# CharlieplexNameTag.net
KiCad netlist of a schematic drawn in EAGLE
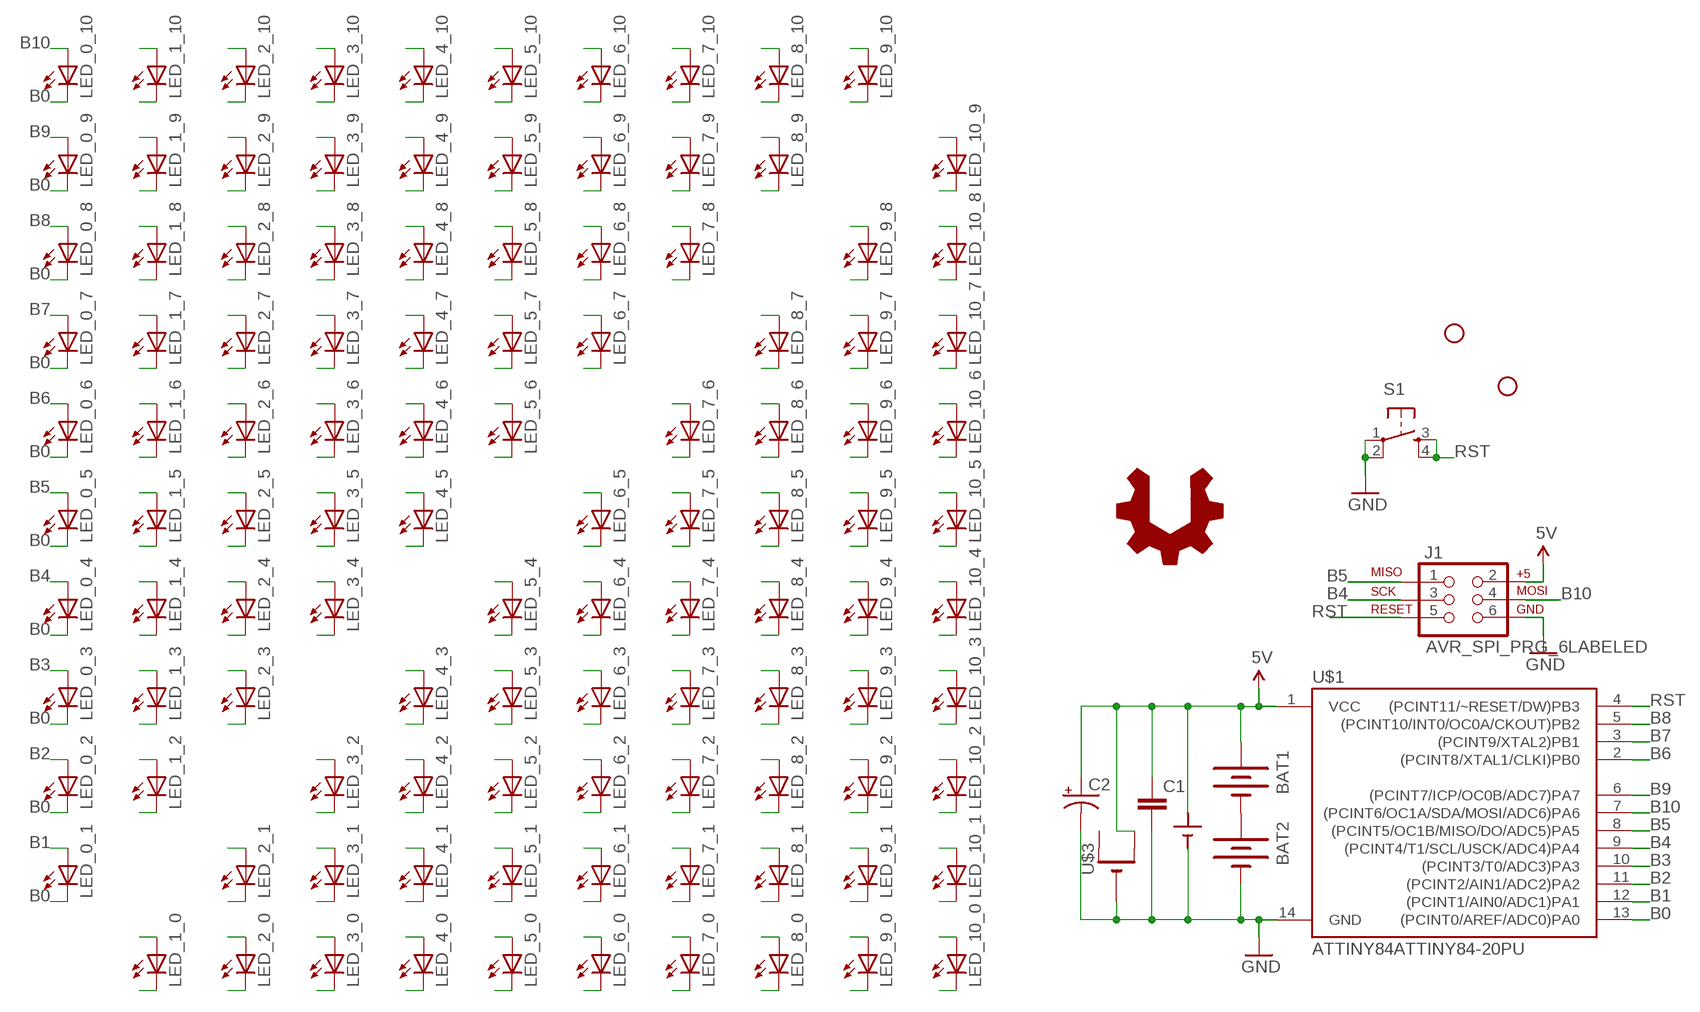
[diagram p0: schematic, sheet 1]

(export (version "E")
  (design (tool "Eeschema 10.0.6"))
  (components
    (comp (ref "BAT1")
      (value "BATTERYAAA")
      (footprint "eagle-import:BATTERY-AAA")
      (libsource (lib "eagle-import") (part "BATTERYAAA"))
    )
    (comp (ref "BAT2")
      (value "BATTERYAAA")
      (footprint "eagle-import:BATTERY-AAA")
      (libsource (lib "eagle-import") (part "BATTERYAAA"))
    )
    (comp (ref "C1")
      (value "CAPPTH")
      (footprint "eagle-import:CAP-PTH-SMALL")
      (libsource (lib "eagle-import") (part "CAPPTH"))
    )
    (comp (ref "C2")
      (value "CAP_POLPTH1")
      (footprint "eagle-import:CPOL-RADIAL-100UF-25V")
      (libsource (lib "eagle-import") (part "CAP_POLPTH1"))
    )
    (comp (ref "J1")
      (value "AVR_SPI_PRG_6LABELED")
      (footprint "eagle-import:2X3-NS")
      (libsource (lib "eagle-import") (part "AVR_SPI_PRG_6LABELED"))
    )
    (comp (ref "LED_0_1")
      (value "LEDOVAL")
      (footprint "eagle-import:LED-OVAL")
      (libsource (lib "eagle-import") (part "LEDOVAL"))
    )
    (comp (ref "LED_0_2")
      (value "LEDOVAL")
      (footprint "eagle-import:LED-OVAL")
      (libsource (lib "eagle-import") (part "LEDOVAL"))
    )
    (comp (ref "LED_0_3")
      (value "LEDOVAL")
      (footprint "eagle-import:LED-OVAL")
      (libsource (lib "eagle-import") (part "LEDOVAL"))
    )
    (comp (ref "LED_0_4")
      (value "LEDOVAL")
      (footprint "eagle-import:LED-OVAL")
      (libsource (lib "eagle-import") (part "LEDOVAL"))
    )
    (comp (ref "LED_0_5")
      (value "LEDOVAL")
      (footprint "eagle-import:LED-OVAL")
      (libsource (lib "eagle-import") (part "LEDOVAL"))
    )
    (comp (ref "LED_0_6")
      (value "LEDOVAL")
      (footprint "eagle-import:LED-OVAL")
      (libsource (lib "eagle-import") (part "LEDOVAL"))
    )
    (comp (ref "LED_0_7")
      (value "LEDOVAL")
      (footprint "eagle-import:LED-OVAL")
      (libsource (lib "eagle-import") (part "LEDOVAL"))
    )
    (comp (ref "LED_0_8")
      (value "LEDOVAL")
      (footprint "eagle-import:LED-OVAL")
      (libsource (lib "eagle-import") (part "LEDOVAL"))
    )
    (comp (ref "LED_0_9")
      (value "LEDOVAL")
      (footprint "eagle-import:LED-OVAL")
      (libsource (lib "eagle-import") (part "LEDOVAL"))
    )
    (comp (ref "LED_0_10")
      (value "LEDOVAL")
      (footprint "eagle-import:LED-OVAL")
      (libsource (lib "eagle-import") (part "LEDOVAL"))
    )
    (comp (ref "LED_1_0")
      (value "LEDOVAL")
      (footprint "eagle-import:LED-OVAL")
      (libsource (lib "eagle-import") (part "LEDOVAL"))
    )
    (comp (ref "LED_1_2")
      (value "LEDOVAL")
      (footprint "eagle-import:LED-OVAL")
      (libsource (lib "eagle-import") (part "LEDOVAL"))
    )
    (comp (ref "LED_1_3")
      (value "LEDOVAL")
      (footprint "eagle-import:LED-OVAL")
      (libsource (lib "eagle-import") (part "LEDOVAL"))
    )
    (comp (ref "LED_1_4")
      (value "LEDOVAL")
      (footprint "eagle-import:LED-OVAL")
      (libsource (lib "eagle-import") (part "LEDOVAL"))
    )
    (comp (ref "LED_1_5")
      (value "LEDOVAL")
      (footprint "eagle-import:LED-OVAL")
      (libsource (lib "eagle-import") (part "LEDOVAL"))
    )
    (comp (ref "LED_1_6")
      (value "LEDOVAL")
      (footprint "eagle-import:LED-OVAL")
      (libsource (lib "eagle-import") (part "LEDOVAL"))
    )
    (comp (ref "LED_1_7")
      (value "LEDOVAL")
      (footprint "eagle-import:LED-OVAL")
      (libsource (lib "eagle-import") (part "LEDOVAL"))
    )
    (comp (ref "LED_1_8")
      (value "LEDOVAL")
      (footprint "eagle-import:LED-OVAL")
      (libsource (lib "eagle-import") (part "LEDOVAL"))
    )
    (comp (ref "LED_1_9")
      (value "LEDOVAL")
      (footprint "eagle-import:LED-OVAL")
      (libsource (lib "eagle-import") (part "LEDOVAL"))
    )
    (comp (ref "LED_1_10")
      (value "LEDOVAL")
      (footprint "eagle-import:LED-OVAL")
      (libsource (lib "eagle-import") (part "LEDOVAL"))
    )
    (comp (ref "LED_2_0")
      (value "LEDOVAL")
      (footprint "eagle-import:LED-OVAL")
      (libsource (lib "eagle-import") (part "LEDOVAL"))
    )
    (comp (ref "LED_2_1")
      (value "LEDOVAL")
      (footprint "eagle-import:LED-OVAL")
      (libsource (lib "eagle-import") (part "LEDOVAL"))
    )
    (comp (ref "LED_2_3")
      (value "LEDOVAL")
      (footprint "eagle-import:LED-OVAL")
      (libsource (lib "eagle-import") (part "LEDOVAL"))
    )
    (comp (ref "LED_2_4")
      (value "LEDOVAL")
      (footprint "eagle-import:LED-OVAL")
      (libsource (lib "eagle-import") (part "LEDOVAL"))
    )
    (comp (ref "LED_2_5")
      (value "LEDOVAL")
      (footprint "eagle-import:LED-OVAL")
      (libsource (lib "eagle-import") (part "LEDOVAL"))
    )
    (comp (ref "LED_2_6")
      (value "LEDOVAL")
      (footprint "eagle-import:LED-OVAL")
      (libsource (lib "eagle-import") (part "LEDOVAL"))
    )
    (comp (ref "LED_2_7")
      (value "LEDOVAL")
      (footprint "eagle-import:LED-OVAL")
      (libsource (lib "eagle-import") (part "LEDOVAL"))
    )
    (comp (ref "LED_2_8")
      (value "LEDOVAL")
      (footprint "eagle-import:LED-OVAL")
      (libsource (lib "eagle-import") (part "LEDOVAL"))
    )
    (comp (ref "LED_2_9")
      (value "LEDOVAL")
      (footprint "eagle-import:LED-OVAL")
      (libsource (lib "eagle-import") (part "LEDOVAL"))
    )
    (comp (ref "LED_2_10")
      (value "LEDOVAL")
      (footprint "eagle-import:LED-OVAL")
      (libsource (lib "eagle-import") (part "LEDOVAL"))
    )
    (comp (ref "LED_3_0")
      (value "LEDOVAL")
      (footprint "eagle-import:LED-OVAL")
      (libsource (lib "eagle-import") (part "LEDOVAL"))
    )
    (comp (ref "LED_3_1")
      (value "LEDOVAL")
      (footprint "eagle-import:LED-OVAL")
      (libsource (lib "eagle-import") (part "LEDOVAL"))
    )
    (comp (ref "LED_3_2")
      (value "LEDOVAL")
      (footprint "eagle-import:LED-OVAL")
      (libsource (lib "eagle-import") (part "LEDOVAL"))
    )
    (comp (ref "LED_3_4")
      (value "LEDOVAL")
      (footprint "eagle-import:LED-OVAL")
      (libsource (lib "eagle-import") (part "LEDOVAL"))
    )
    (comp (ref "LED_3_5")
      (value "LEDOVAL")
      (footprint "eagle-import:LED-OVAL")
      (libsource (lib "eagle-import") (part "LEDOVAL"))
    )
    (comp (ref "LED_3_6")
      (value "LEDOVAL")
      (footprint "eagle-import:LED-OVAL")
      (libsource (lib "eagle-import") (part "LEDOVAL"))
    )
    (comp (ref "LED_3_7")
      (value "LEDOVAL")
      (footprint "eagle-import:LED-OVAL")
      (libsource (lib "eagle-import") (part "LEDOVAL"))
    )
    (comp (ref "LED_3_8")
      (value "LEDOVAL")
      (footprint "eagle-import:LED-OVAL")
      (libsource (lib "eagle-import") (part "LEDOVAL"))
    )
    (comp (ref "LED_3_9")
      (value "LEDOVAL")
      (footprint "eagle-import:LED-OVAL")
      (libsource (lib "eagle-import") (part "LEDOVAL"))
    )
    (comp (ref "LED_3_10")
      (value "LEDOVAL")
      (footprint "eagle-import:LED-OVAL")
      (libsource (lib "eagle-import") (part "LEDOVAL"))
    )
    (comp (ref "LED_4_0")
      (value "LEDOVAL")
      (footprint "eagle-import:LED-OVAL")
      (libsource (lib "eagle-import") (part "LEDOVAL"))
    )
    (comp (ref "LED_4_1")
      (value "LEDOVAL")
      (footprint "eagle-import:LED-OVAL")
      (libsource (lib "eagle-import") (part "LEDOVAL"))
    )
    (comp (ref "LED_4_2")
      (value "LEDOVAL")
      (footprint "eagle-import:LED-OVAL")
      (libsource (lib "eagle-import") (part "LEDOVAL"))
    )
    (comp (ref "LED_4_3")
      (value "LEDOVAL")
      (footprint "eagle-import:LED-OVAL")
      (libsource (lib "eagle-import") (part "LEDOVAL"))
    )
    (comp (ref "LED_4_5")
      (value "LEDOVAL")
      (footprint "eagle-import:LED-OVAL")
      (libsource (lib "eagle-import") (part "LEDOVAL"))
    )
    (comp (ref "LED_4_6")
      (value "LEDOVAL")
      (footprint "eagle-import:LED-OVAL")
      (libsource (lib "eagle-import") (part "LEDOVAL"))
    )
    (comp (ref "LED_4_7")
      (value "LEDOVAL")
      (footprint "eagle-import:LED-OVAL")
      (libsource (lib "eagle-import") (part "LEDOVAL"))
    )
    (comp (ref "LED_4_8")
      (value "LEDOVAL")
      (footprint "eagle-import:LED-OVAL")
      (libsource (lib "eagle-import") (part "LEDOVAL"))
    )
    (comp (ref "LED_4_9")
      (value "LEDOVAL")
      (footprint "eagle-import:LED-OVAL")
      (libsource (lib "eagle-import") (part "LEDOVAL"))
    )
    (comp (ref "LED_4_10")
      (value "LEDOVAL")
      (footprint "eagle-import:LED-OVAL")
      (libsource (lib "eagle-import") (part "LEDOVAL"))
    )
    (comp (ref "LED_5_0")
      (value "LEDOVAL")
      (footprint "eagle-import:LED-OVAL")
      (libsource (lib "eagle-import") (part "LEDOVAL"))
    )
    (comp (ref "LED_5_1")
      (value "LEDOVAL")
      (footprint "eagle-import:LED-OVAL")
      (libsource (lib "eagle-import") (part "LEDOVAL"))
    )
    (comp (ref "LED_5_2")
      (value "LEDOVAL")
      (footprint "eagle-import:LED-OVAL")
      (libsource (lib "eagle-import") (part "LEDOVAL"))
    )
    (comp (ref "LED_5_3")
      (value "LEDOVAL")
      (footprint "eagle-import:LED-OVAL")
      (libsource (lib "eagle-import") (part "LEDOVAL"))
    )
    (comp (ref "LED_5_4")
      (value "LEDOVAL")
      (footprint "eagle-import:LED-OVAL")
      (libsource (lib "eagle-import") (part "LEDOVAL"))
    )
    (comp (ref "LED_5_6")
      (value "LEDOVAL")
      (footprint "eagle-import:LED-OVAL")
      (libsource (lib "eagle-import") (part "LEDOVAL"))
    )
    (comp (ref "LED_5_7")
      (value "LEDOVAL")
      (footprint "eagle-import:LED-OVAL")
      (libsource (lib "eagle-import") (part "LEDOVAL"))
    )
    (comp (ref "LED_5_8")
      (value "LEDOVAL")
      (footprint "eagle-import:LED-OVAL")
      (libsource (lib "eagle-import") (part "LEDOVAL"))
    )
    (comp (ref "LED_5_9")
      (value "LEDOVAL")
      (footprint "eagle-import:LED-OVAL")
      (libsource (lib "eagle-import") (part "LEDOVAL"))
    )
    (comp (ref "LED_5_10")
      (value "LEDOVAL")
      (footprint "eagle-import:LED-OVAL")
      (libsource (lib "eagle-import") (part "LEDOVAL"))
    )
    (comp (ref "LED_6_0")
      (value "LEDOVAL")
      (footprint "eagle-import:LED-OVAL")
      (libsource (lib "eagle-import") (part "LEDOVAL"))
    )
    (comp (ref "LED_6_1")
      (value "LEDOVAL")
      (footprint "eagle-import:LED-OVAL")
      (libsource (lib "eagle-import") (part "LEDOVAL"))
    )
    (comp (ref "LED_6_2")
      (value "LEDOVAL")
      (footprint "eagle-import:LED-OVAL")
      (libsource (lib "eagle-import") (part "LEDOVAL"))
    )
    (comp (ref "LED_6_3")
      (value "LEDOVAL")
      (footprint "eagle-import:LED-OVAL")
      (libsource (lib "eagle-import") (part "LEDOVAL"))
    )
    (comp (ref "LED_6_4")
      (value "LEDOVAL")
      (footprint "eagle-import:LED-OVAL")
      (libsource (lib "eagle-import") (part "LEDOVAL"))
    )
    (comp (ref "LED_6_5")
      (value "LEDOVAL")
      (footprint "eagle-import:LED-OVAL")
      (libsource (lib "eagle-import") (part "LEDOVAL"))
    )
    (comp (ref "LED_6_7")
      (value "LEDOVAL")
      (footprint "eagle-import:LED-OVAL")
      (libsource (lib "eagle-import") (part "LEDOVAL"))
    )
    (comp (ref "LED_6_8")
      (value "LEDOVAL")
      (footprint "eagle-import:LED-OVAL")
      (libsource (lib "eagle-import") (part "LEDOVAL"))
    )
    (comp (ref "LED_6_9")
      (value "LEDOVAL")
      (footprint "eagle-import:LED-OVAL")
      (libsource (lib "eagle-import") (part "LEDOVAL"))
    )
    (comp (ref "LED_6_10")
      (value "LEDOVAL")
      (footprint "eagle-import:LED-OVAL")
      (libsource (lib "eagle-import") (part "LEDOVAL"))
    )
    (comp (ref "LED_7_0")
      (value "LEDOVAL")
      (footprint "eagle-import:LED-OVAL")
      (libsource (lib "eagle-import") (part "LEDOVAL"))
    )
    (comp (ref "LED_7_1")
      (value "LEDOVAL")
      (footprint "eagle-import:LED-OVAL")
      (libsource (lib "eagle-import") (part "LEDOVAL"))
    )
    (comp (ref "LED_7_2")
      (value "LEDOVAL")
      (footprint "eagle-import:LED-OVAL")
      (libsource (lib "eagle-import") (part "LEDOVAL"))
    )
    (comp (ref "LED_7_3")
      (value "LEDOVAL")
      (footprint "eagle-import:LED-OVAL")
      (libsource (lib "eagle-import") (part "LEDOVAL"))
    )
    (comp (ref "LED_7_4")
      (value "LEDOVAL")
      (footprint "eagle-import:LED-OVAL")
      (libsource (lib "eagle-import") (part "LEDOVAL"))
    )
    (comp (ref "LED_7_5")
      (value "LEDOVAL")
      (footprint "eagle-import:LED-OVAL")
      (libsource (lib "eagle-import") (part "LEDOVAL"))
    )
    (comp (ref "LED_7_6")
      (value "LEDOVAL")
      (footprint "eagle-import:LED-OVAL")
      (libsource (lib "eagle-import") (part "LEDOVAL"))
    )
    (comp (ref "LED_7_8")
      (value "LEDOVAL")
      (footprint "eagle-import:LED-OVAL")
      (libsource (lib "eagle-import") (part "LEDOVAL"))
    )
    (comp (ref "LED_7_9")
      (value "LEDOVAL")
      (footprint "eagle-import:LED-OVAL")
      (libsource (lib "eagle-import") (part "LEDOVAL"))
    )
    (comp (ref "LED_7_10")
      (value "LEDOVAL")
      (footprint "eagle-import:LED-OVAL")
      (libsource (lib "eagle-import") (part "LEDOVAL"))
    )
    (comp (ref "LED_8_0")
      (value "LEDOVAL")
      (footprint "eagle-import:LED-OVAL")
      (libsource (lib "eagle-import") (part "LEDOVAL"))
    )
    (comp (ref "LED_8_1")
      (value "LEDOVAL")
      (footprint "eagle-import:LED-OVAL")
      (libsource (lib "eagle-import") (part "LEDOVAL"))
    )
    (comp (ref "LED_8_2")
      (value "LEDOVAL")
      (footprint "eagle-import:LED-OVAL")
      (libsource (lib "eagle-import") (part "LEDOVAL"))
    )
    (comp (ref "LED_8_3")
      (value "LEDOVAL")
      (footprint "eagle-import:LED-OVAL")
      (libsource (lib "eagle-import") (part "LEDOVAL"))
    )
    (comp (ref "LED_8_4")
      (value "LEDOVAL")
      (footprint "eagle-import:LED-OVAL")
      (libsource (lib "eagle-import") (part "LEDOVAL"))
    )
    (comp (ref "LED_8_5")
      (value "LEDOVAL")
      (footprint "eagle-import:LED-OVAL")
      (libsource (lib "eagle-import") (part "LEDOVAL"))
    )
    (comp (ref "LED_8_6")
      (value "LEDOVAL")
      (footprint "eagle-import:LED-OVAL")
      (libsource (lib "eagle-import") (part "LEDOVAL"))
    )
    (comp (ref "LED_8_7")
      (value "LEDOVAL")
      (footprint "eagle-import:LED-OVAL")
      (libsource (lib "eagle-import") (part "LEDOVAL"))
    )
    (comp (ref "LED_8_9")
      (value "LEDOVAL")
      (footprint "eagle-import:LED-OVAL")
      (libsource (lib "eagle-import") (part "LEDOVAL"))
    )
    (comp (ref "LED_8_10")
      (value "LEDOVAL")
      (footprint "eagle-import:LED-OVAL")
      (libsource (lib "eagle-import") (part "LEDOVAL"))
    )
    (comp (ref "LED_9_0")
      (value "LEDOVAL")
      (footprint "eagle-import:LED-OVAL")
      (libsource (lib "eagle-import") (part "LEDOVAL"))
    )
    (comp (ref "LED_9_1")
      (value "LEDOVAL")
      (footprint "eagle-import:LED-OVAL")
      (libsource (lib "eagle-import") (part "LEDOVAL"))
    )
    (comp (ref "LED_9_2")
      (value "LEDOVAL")
      (footprint "eagle-import:LED-OVAL")
      (libsource (lib "eagle-import") (part "LEDOVAL"))
    )
    (comp (ref "LED_9_3")
      (value "LEDOVAL")
      (footprint "eagle-import:LED-OVAL")
      (libsource (lib "eagle-import") (part "LEDOVAL"))
    )
    (comp (ref "LED_9_4")
      (value "LEDOVAL")
      (footprint "eagle-import:LED-OVAL")
      (libsource (lib "eagle-import") (part "LEDOVAL"))
    )
    (comp (ref "LED_9_5")
      (value "LEDOVAL")
      (footprint "eagle-import:LED-OVAL")
      (libsource (lib "eagle-import") (part "LEDOVAL"))
    )
    (comp (ref "LED_9_6")
      (value "LEDOVAL")
      (footprint "eagle-import:LED-OVAL")
      (libsource (lib "eagle-import") (part "LEDOVAL"))
    )
    (comp (ref "LED_9_7")
      (value "LEDOVAL")
      (footprint "eagle-import:LED-OVAL")
      (libsource (lib "eagle-import") (part "LEDOVAL"))
    )
    (comp (ref "LED_9_8")
      (value "LEDOVAL")
      (footprint "eagle-import:LED-OVAL")
      (libsource (lib "eagle-import") (part "LEDOVAL"))
    )
    (comp (ref "LED_9_10")
      (value "LEDOVAL")
      (footprint "eagle-import:LED-OVAL")
      (libsource (lib "eagle-import") (part "LEDOVAL"))
    )
    (comp (ref "LED_10_0")
      (value "LEDOVAL")
      (footprint "eagle-import:LED-OVAL")
      (libsource (lib "eagle-import") (part "LEDOVAL"))
    )
    (comp (ref "LED_10_1")
      (value "LEDOVAL")
      (footprint "eagle-import:LED-OVAL")
      (libsource (lib "eagle-import") (part "LEDOVAL"))
    )
    (comp (ref "LED_10_2")
      (value "LEDOVAL")
      (footprint "eagle-import:LED-OVAL")
      (libsource (lib "eagle-import") (part "LEDOVAL"))
    )
    (comp (ref "LED_10_3")
      (value "LEDOVAL")
      (footprint "eagle-import:LED-OVAL")
      (libsource (lib "eagle-import") (part "LEDOVAL"))
    )
    (comp (ref "LED_10_4")
      (value "LEDOVAL")
      (footprint "eagle-import:LED-OVAL")
      (libsource (lib "eagle-import") (part "LEDOVAL"))
    )
    (comp (ref "LED_10_5")
      (value "LEDOVAL")
      (footprint "eagle-import:LED-OVAL")
      (libsource (lib "eagle-import") (part "LEDOVAL"))
    )
    (comp (ref "LED_10_6")
      (value "LEDOVAL")
      (footprint "eagle-import:LED-OVAL")
      (libsource (lib "eagle-import") (part "LEDOVAL"))
    )
    (comp (ref "LED_10_7")
      (value "LEDOVAL")
      (footprint "eagle-import:LED-OVAL")
      (libsource (lib "eagle-import") (part "LEDOVAL"))
    )
    (comp (ref "LED_10_8")
      (value "LEDOVAL")
      (footprint "eagle-import:LED-OVAL")
      (libsource (lib "eagle-import") (part "LEDOVAL"))
    )
    (comp (ref "LED_10_9")
      (value "LEDOVAL")
      (footprint "eagle-import:LED-OVAL")
      (libsource (lib "eagle-import") (part "LEDOVAL"))
    )
    (comp (ref "S1")
      (value "TAC_SWITCHPTH")
      (footprint "eagle-import:TACTILE-PTH")
      (libsource (lib "eagle-import") (part "TAC_SWITCHPTH"))
    )
    (comp (ref "STANDOFF1")
      (value "STAND-OFF")
      (footprint "eagle-import:STAND-OFF")
      (libsource (lib "eagle-import") (part "STAND-OFF"))
    )
    (comp (ref "STANDOFF4")
      (value "STAND-OFF")
      (footprint "eagle-import:STAND-OFF")
      (libsource (lib "eagle-import") (part "STAND-OFF"))
    )
    (comp (ref "U$1")
      (value "ATTINY84ATTINY84-20PU")
      (footprint "eagle-import:DIL14")
      (libsource (lib "eagle-import") (part "ATTINY84ATTINY84-20PU"))
    )
    (comp (ref "U$2")
      (value "BATT2AAA")
      (footprint "eagle-import:BC2AAAPC")
      (libsource (lib "eagle-import") (part "BATT2AAA"))
    )
    (comp (ref "U$3")
      (value "CR2032THM")
      (footprint "eagle-import:CR2032-THRU")
      (libsource (lib "eagle-import") (part "CR2032THM"))
    )
    (comp (ref "U$4")
      (value "USER_HACKABLE")
      (footprint "eagle-import:USER_HACKABLE")
      (libsource (lib "eagle-import") (part "USER_HACKABLE"))
    )
  )
  (nets
    (net (code "1") (name "/B0") (class "Default")
      (node (ref "LED_0_1") (pin "CATHODE") (pinfunction "C_CATHODE") (pintype "passive"))
      (node (ref "LED_0_10") (pin "CATHODE") (pinfunction "C_CATHODE") (pintype "passive"))
      (node (ref "LED_0_2") (pin "CATHODE") (pinfunction "C_CATHODE") (pintype "passive"))
      (node (ref "LED_0_3") (pin "CATHODE") (pinfunction "C_CATHODE") (pintype "passive"))
      (node (ref "LED_0_4") (pin "CATHODE") (pinfunction "C_CATHODE") (pintype "passive"))
      (node (ref "LED_0_5") (pin "CATHODE") (pinfunction "C_CATHODE") (pintype "passive"))
      (node (ref "LED_0_6") (pin "CATHODE") (pinfunction "C_CATHODE") (pintype "passive"))
      (node (ref "LED_0_7") (pin "CATHODE") (pinfunction "C_CATHODE") (pintype "passive"))
      (node (ref "LED_0_8") (pin "CATHODE") (pinfunction "C_CATHODE") (pintype "passive"))
      (node (ref "LED_0_9") (pin "CATHODE") (pinfunction "C_CATHODE") (pintype "passive"))
      (node (ref "LED_10_0") (pin "ANODE") (pinfunction "A_ANODE") (pintype "passive"))
      (node (ref "LED_1_0") (pin "ANODE") (pinfunction "A_ANODE") (pintype "passive"))
      (node (ref "LED_2_0") (pin "ANODE") (pinfunction "A_ANODE") (pintype "passive"))
      (node (ref "LED_3_0") (pin "ANODE") (pinfunction "A_ANODE") (pintype "passive"))
      (node (ref "LED_4_0") (pin "ANODE") (pinfunction "A_ANODE") (pintype "passive"))
      (node (ref "LED_5_0") (pin "ANODE") (pinfunction "A_ANODE") (pintype "passive"))
      (node (ref "LED_6_0") (pin "ANODE") (pinfunction "A_ANODE") (pintype "passive"))
      (node (ref "LED_7_0") (pin "ANODE") (pinfunction "A_ANODE") (pintype "passive"))
      (node (ref "LED_8_0") (pin "ANODE") (pinfunction "A_ANODE") (pintype "passive"))
      (node (ref "LED_9_0") (pin "ANODE") (pinfunction "A_ANODE") (pintype "passive"))
      (node (ref "U$1") (pin "13") (pinfunction "(PCINT0/AREF/ADC0)PA0_13") (pintype "bidirectional"))
    )
    (net (code "2") (name "/B1") (class "Default")
      (node (ref "LED_0_1") (pin "ANODE") (pinfunction "A_ANODE") (pintype "passive"))
      (node (ref "LED_10_1") (pin "ANODE") (pinfunction "A_ANODE") (pintype "passive"))
      (node (ref "LED_1_0") (pin "CATHODE") (pinfunction "C_CATHODE") (pintype "passive"))
      (node (ref "LED_1_10") (pin "CATHODE") (pinfunction "C_CATHODE") (pintype "passive"))
      (node (ref "LED_1_2") (pin "CATHODE") (pinfunction "C_CATHODE") (pintype "passive"))
      (node (ref "LED_1_3") (pin "CATHODE") (pinfunction "C_CATHODE") (pintype "passive"))
      (node (ref "LED_1_4") (pin "CATHODE") (pinfunction "C_CATHODE") (pintype "passive"))
      (node (ref "LED_1_5") (pin "CATHODE") (pinfunction "C_CATHODE") (pintype "passive"))
      (node (ref "LED_1_6") (pin "CATHODE") (pinfunction "C_CATHODE") (pintype "passive"))
      (node (ref "LED_1_7") (pin "CATHODE") (pinfunction "C_CATHODE") (pintype "passive"))
      (node (ref "LED_1_8") (pin "CATHODE") (pinfunction "C_CATHODE") (pintype "passive"))
      (node (ref "LED_1_9") (pin "CATHODE") (pinfunction "C_CATHODE") (pintype "passive"))
      (node (ref "LED_2_1") (pin "ANODE") (pinfunction "A_ANODE") (pintype "passive"))
      (node (ref "LED_3_1") (pin "ANODE") (pinfunction "A_ANODE") (pintype "passive"))
      (node (ref "LED_4_1") (pin "ANODE") (pinfunction "A_ANODE") (pintype "passive"))
      (node (ref "LED_5_1") (pin "ANODE") (pinfunction "A_ANODE") (pintype "passive"))
      (node (ref "LED_6_1") (pin "ANODE") (pinfunction "A_ANODE") (pintype "passive"))
      (node (ref "LED_7_1") (pin "ANODE") (pinfunction "A_ANODE") (pintype "passive"))
      (node (ref "LED_8_1") (pin "ANODE") (pinfunction "A_ANODE") (pintype "passive"))
      (node (ref "LED_9_1") (pin "ANODE") (pinfunction "A_ANODE") (pintype "passive"))
      (node (ref "U$1") (pin "12") (pinfunction "(PCINT1/AIN0/ADC1)PA1_12") (pintype "bidirectional"))
    )
    (net (code "3") (name "/B2") (class "Default")
      (node (ref "LED_0_2") (pin "ANODE") (pinfunction "A_ANODE") (pintype "passive"))
      (node (ref "LED_10_2") (pin "ANODE") (pinfunction "A_ANODE") (pintype "passive"))
      (node (ref "LED_1_2") (pin "ANODE") (pinfunction "A_ANODE") (pintype "passive"))
      (node (ref "LED_2_0") (pin "CATHODE") (pinfunction "C_CATHODE") (pintype "passive"))
      (node (ref "LED_2_1") (pin "CATHODE") (pinfunction "C_CATHODE") (pintype "passive"))
      (node (ref "LED_2_10") (pin "CATHODE") (pinfunction "C_CATHODE") (pintype "passive"))
      (node (ref "LED_2_3") (pin "CATHODE") (pinfunction "C_CATHODE") (pintype "passive"))
      (node (ref "LED_2_4") (pin "CATHODE") (pinfunction "C_CATHODE") (pintype "passive"))
      (node (ref "LED_2_5") (pin "CATHODE") (pinfunction "C_CATHODE") (pintype "passive"))
      (node (ref "LED_2_6") (pin "CATHODE") (pinfunction "C_CATHODE") (pintype "passive"))
      (node (ref "LED_2_7") (pin "CATHODE") (pinfunction "C_CATHODE") (pintype "passive"))
      (node (ref "LED_2_8") (pin "CATHODE") (pinfunction "C_CATHODE") (pintype "passive"))
      (node (ref "LED_2_9") (pin "CATHODE") (pinfunction "C_CATHODE") (pintype "passive"))
      (node (ref "LED_3_2") (pin "ANODE") (pinfunction "A_ANODE") (pintype "passive"))
      (node (ref "LED_4_2") (pin "ANODE") (pinfunction "A_ANODE") (pintype "passive"))
      (node (ref "LED_5_2") (pin "ANODE") (pinfunction "A_ANODE") (pintype "passive"))
      (node (ref "LED_6_2") (pin "ANODE") (pinfunction "A_ANODE") (pintype "passive"))
      (node (ref "LED_7_2") (pin "ANODE") (pinfunction "A_ANODE") (pintype "passive"))
      (node (ref "LED_8_2") (pin "ANODE") (pinfunction "A_ANODE") (pintype "passive"))
      (node (ref "LED_9_2") (pin "ANODE") (pinfunction "A_ANODE") (pintype "passive"))
      (node (ref "U$1") (pin "11") (pinfunction "(PCINT2/AIN1/ADC2)PA2_11") (pintype "bidirectional"))
    )
    (net (code "4") (name "/B3") (class "Default")
      (node (ref "LED_0_3") (pin "ANODE") (pinfunction "A_ANODE") (pintype "passive"))
      (node (ref "LED_10_3") (pin "ANODE") (pinfunction "A_ANODE") (pintype "passive"))
      (node (ref "LED_1_3") (pin "ANODE") (pinfunction "A_ANODE") (pintype "passive"))
      (node (ref "LED_2_3") (pin "ANODE") (pinfunction "A_ANODE") (pintype "passive"))
      (node (ref "LED_3_0") (pin "CATHODE") (pinfunction "C_CATHODE") (pintype "passive"))
      (node (ref "LED_3_1") (pin "CATHODE") (pinfunction "C_CATHODE") (pintype "passive"))
      (node (ref "LED_3_10") (pin "CATHODE") (pinfunction "C_CATHODE") (pintype "passive"))
      (node (ref "LED_3_2") (pin "CATHODE") (pinfunction "C_CATHODE") (pintype "passive"))
      (node (ref "LED_3_4") (pin "CATHODE") (pinfunction "C_CATHODE") (pintype "passive"))
      (node (ref "LED_3_5") (pin "CATHODE") (pinfunction "C_CATHODE") (pintype "passive"))
      (node (ref "LED_3_6") (pin "CATHODE") (pinfunction "C_CATHODE") (pintype "passive"))
      (node (ref "LED_3_7") (pin "CATHODE") (pinfunction "C_CATHODE") (pintype "passive"))
      (node (ref "LED_3_8") (pin "CATHODE") (pinfunction "C_CATHODE") (pintype "passive"))
      (node (ref "LED_3_9") (pin "CATHODE") (pinfunction "C_CATHODE") (pintype "passive"))
      (node (ref "LED_4_3") (pin "ANODE") (pinfunction "A_ANODE") (pintype "passive"))
      (node (ref "LED_5_3") (pin "ANODE") (pinfunction "A_ANODE") (pintype "passive"))
      (node (ref "LED_6_3") (pin "ANODE") (pinfunction "A_ANODE") (pintype "passive"))
      (node (ref "LED_7_3") (pin "ANODE") (pinfunction "A_ANODE") (pintype "passive"))
      (node (ref "LED_8_3") (pin "ANODE") (pinfunction "A_ANODE") (pintype "passive"))
      (node (ref "LED_9_3") (pin "ANODE") (pinfunction "A_ANODE") (pintype "passive"))
      (node (ref "U$1") (pin "10") (pinfunction "(PCINT3/T0/ADC3)PA3_10") (pintype "bidirectional"))
    )
    (net (code "5") (name "/B4") (class "Default")
      (node (ref "J1") (pin "3") (pinfunction "SCK_3") (pintype "passive"))
      (node (ref "LED_0_4") (pin "ANODE") (pinfunction "A_ANODE") (pintype "passive"))
      (node (ref "LED_10_4") (pin "ANODE") (pinfunction "A_ANODE") (pintype "passive"))
      (node (ref "LED_1_4") (pin "ANODE") (pinfunction "A_ANODE") (pintype "passive"))
      (node (ref "LED_2_4") (pin "ANODE") (pinfunction "A_ANODE") (pintype "passive"))
      (node (ref "LED_3_4") (pin "ANODE") (pinfunction "A_ANODE") (pintype "passive"))
      (node (ref "LED_4_0") (pin "CATHODE") (pinfunction "C_CATHODE") (pintype "passive"))
      (node (ref "LED_4_1") (pin "CATHODE") (pinfunction "C_CATHODE") (pintype "passive"))
      (node (ref "LED_4_10") (pin "CATHODE") (pinfunction "C_CATHODE") (pintype "passive"))
      (node (ref "LED_4_2") (pin "CATHODE") (pinfunction "C_CATHODE") (pintype "passive"))
      (node (ref "LED_4_3") (pin "CATHODE") (pinfunction "C_CATHODE") (pintype "passive"))
      (node (ref "LED_4_5") (pin "CATHODE") (pinfunction "C_CATHODE") (pintype "passive"))
      (node (ref "LED_4_6") (pin "CATHODE") (pinfunction "C_CATHODE") (pintype "passive"))
      (node (ref "LED_4_7") (pin "CATHODE") (pinfunction "C_CATHODE") (pintype "passive"))
      (node (ref "LED_4_8") (pin "CATHODE") (pinfunction "C_CATHODE") (pintype "passive"))
      (node (ref "LED_4_9") (pin "CATHODE") (pinfunction "C_CATHODE") (pintype "passive"))
      (node (ref "LED_5_4") (pin "ANODE") (pinfunction "A_ANODE") (pintype "passive"))
      (node (ref "LED_6_4") (pin "ANODE") (pinfunction "A_ANODE") (pintype "passive"))
      (node (ref "LED_7_4") (pin "ANODE") (pinfunction "A_ANODE") (pintype "passive"))
      (node (ref "LED_8_4") (pin "ANODE") (pinfunction "A_ANODE") (pintype "passive"))
      (node (ref "LED_9_4") (pin "ANODE") (pinfunction "A_ANODE") (pintype "passive"))
      (node (ref "U$1") (pin "9") (pinfunction "(PCINT4/T1/SCL/USCK/ADC4)PA4_9") (pintype "bidirectional"))
    )
    (net (code "6") (name "/B5") (class "Default")
      (node (ref "J1") (pin "1") (pinfunction "MISO_1") (pintype "passive"))
      (node (ref "LED_0_5") (pin "ANODE") (pinfunction "A_ANODE") (pintype "passive"))
      (node (ref "LED_10_5") (pin "ANODE") (pinfunction "A_ANODE") (pintype "passive"))
      (node (ref "LED_1_5") (pin "ANODE") (pinfunction "A_ANODE") (pintype "passive"))
      (node (ref "LED_2_5") (pin "ANODE") (pinfunction "A_ANODE") (pintype "passive"))
      (node (ref "LED_3_5") (pin "ANODE") (pinfunction "A_ANODE") (pintype "passive"))
      (node (ref "LED_4_5") (pin "ANODE") (pinfunction "A_ANODE") (pintype "passive"))
      (node (ref "LED_5_0") (pin "CATHODE") (pinfunction "C_CATHODE") (pintype "passive"))
      (node (ref "LED_5_1") (pin "CATHODE") (pinfunction "C_CATHODE") (pintype "passive"))
      (node (ref "LED_5_10") (pin "CATHODE") (pinfunction "C_CATHODE") (pintype "passive"))
      (node (ref "LED_5_2") (pin "CATHODE") (pinfunction "C_CATHODE") (pintype "passive"))
      (node (ref "LED_5_3") (pin "CATHODE") (pinfunction "C_CATHODE") (pintype "passive"))
      (node (ref "LED_5_4") (pin "CATHODE") (pinfunction "C_CATHODE") (pintype "passive"))
      (node (ref "LED_5_6") (pin "CATHODE") (pinfunction "C_CATHODE") (pintype "passive"))
      (node (ref "LED_5_7") (pin "CATHODE") (pinfunction "C_CATHODE") (pintype "passive"))
      (node (ref "LED_5_8") (pin "CATHODE") (pinfunction "C_CATHODE") (pintype "passive"))
      (node (ref "LED_5_9") (pin "CATHODE") (pinfunction "C_CATHODE") (pintype "passive"))
      (node (ref "LED_6_5") (pin "ANODE") (pinfunction "A_ANODE") (pintype "passive"))
      (node (ref "LED_7_5") (pin "ANODE") (pinfunction "A_ANODE") (pintype "passive"))
      (node (ref "LED_8_5") (pin "ANODE") (pinfunction "A_ANODE") (pintype "passive"))
      (node (ref "LED_9_5") (pin "ANODE") (pinfunction "A_ANODE") (pintype "passive"))
      (node (ref "U$1") (pin "8") (pinfunction "(PCINT5/OC1B/MISO/DO/ADC5)PA5_8") (pintype "bidirectional"))
    )
    (net (code "7") (name "/B6") (class "Default")
      (node (ref "LED_0_6") (pin "ANODE") (pinfunction "A_ANODE") (pintype "passive"))
      (node (ref "LED_10_6") (pin "ANODE") (pinfunction "A_ANODE") (pintype "passive"))
      (node (ref "LED_1_6") (pin "ANODE") (pinfunction "A_ANODE") (pintype "passive"))
      (node (ref "LED_2_6") (pin "ANODE") (pinfunction "A_ANODE") (pintype "passive"))
      (node (ref "LED_3_6") (pin "ANODE") (pinfunction "A_ANODE") (pintype "passive"))
      (node (ref "LED_4_6") (pin "ANODE") (pinfunction "A_ANODE") (pintype "passive"))
      (node (ref "LED_5_6") (pin "ANODE") (pinfunction "A_ANODE") (pintype "passive"))
      (node (ref "LED_6_0") (pin "CATHODE") (pinfunction "C_CATHODE") (pintype "passive"))
      (node (ref "LED_6_1") (pin "CATHODE") (pinfunction "C_CATHODE") (pintype "passive"))
      (node (ref "LED_6_10") (pin "CATHODE") (pinfunction "C_CATHODE") (pintype "passive"))
      (node (ref "LED_6_2") (pin "CATHODE") (pinfunction "C_CATHODE") (pintype "passive"))
      (node (ref "LED_6_3") (pin "CATHODE") (pinfunction "C_CATHODE") (pintype "passive"))
      (node (ref "LED_6_4") (pin "CATHODE") (pinfunction "C_CATHODE") (pintype "passive"))
      (node (ref "LED_6_5") (pin "CATHODE") (pinfunction "C_CATHODE") (pintype "passive"))
      (node (ref "LED_6_7") (pin "CATHODE") (pinfunction "C_CATHODE") (pintype "passive"))
      (node (ref "LED_6_8") (pin "CATHODE") (pinfunction "C_CATHODE") (pintype "passive"))
      (node (ref "LED_6_9") (pin "CATHODE") (pinfunction "C_CATHODE") (pintype "passive"))
      (node (ref "LED_7_6") (pin "ANODE") (pinfunction "A_ANODE") (pintype "passive"))
      (node (ref "LED_8_6") (pin "ANODE") (pinfunction "A_ANODE") (pintype "passive"))
      (node (ref "LED_9_6") (pin "ANODE") (pinfunction "A_ANODE") (pintype "passive"))
      (node (ref "U$1") (pin "2") (pinfunction "(PCINT8/XTAL1/CLKI)PB0_2") (pintype "bidirectional"))
    )
    (net (code "8") (name "/B7") (class "Default")
      (node (ref "LED_0_7") (pin "ANODE") (pinfunction "A_ANODE") (pintype "passive"))
      (node (ref "LED_10_7") (pin "ANODE") (pinfunction "A_ANODE") (pintype "passive"))
      (node (ref "LED_1_7") (pin "ANODE") (pinfunction "A_ANODE") (pintype "passive"))
      (node (ref "LED_2_7") (pin "ANODE") (pinfunction "A_ANODE") (pintype "passive"))
      (node (ref "LED_3_7") (pin "ANODE") (pinfunction "A_ANODE") (pintype "passive"))
      (node (ref "LED_4_7") (pin "ANODE") (pinfunction "A_ANODE") (pintype "passive"))
      (node (ref "LED_5_7") (pin "ANODE") (pinfunction "A_ANODE") (pintype "passive"))
      (node (ref "LED_6_7") (pin "ANODE") (pinfunction "A_ANODE") (pintype "passive"))
      (node (ref "LED_7_0") (pin "CATHODE") (pinfunction "C_CATHODE") (pintype "passive"))
      (node (ref "LED_7_1") (pin "CATHODE") (pinfunction "C_CATHODE") (pintype "passive"))
      (node (ref "LED_7_10") (pin "CATHODE") (pinfunction "C_CATHODE") (pintype "passive"))
      (node (ref "LED_7_2") (pin "CATHODE") (pinfunction "C_CATHODE") (pintype "passive"))
      (node (ref "LED_7_3") (pin "CATHODE") (pinfunction "C_CATHODE") (pintype "passive"))
      (node (ref "LED_7_4") (pin "CATHODE") (pinfunction "C_CATHODE") (pintype "passive"))
      (node (ref "LED_7_5") (pin "CATHODE") (pinfunction "C_CATHODE") (pintype "passive"))
      (node (ref "LED_7_6") (pin "CATHODE") (pinfunction "C_CATHODE") (pintype "passive"))
      (node (ref "LED_7_8") (pin "CATHODE") (pinfunction "C_CATHODE") (pintype "passive"))
      (node (ref "LED_7_9") (pin "CATHODE") (pinfunction "C_CATHODE") (pintype "passive"))
      (node (ref "LED_8_7") (pin "ANODE") (pinfunction "A_ANODE") (pintype "passive"))
      (node (ref "LED_9_7") (pin "ANODE") (pinfunction "A_ANODE") (pintype "passive"))
      (node (ref "U$1") (pin "3") (pinfunction "(PCINT9/XTAL2)PB1_3") (pintype "bidirectional"))
    )
    (net (code "9") (name "/B8") (class "Default")
      (node (ref "LED_0_8") (pin "ANODE") (pinfunction "A_ANODE") (pintype "passive"))
      (node (ref "LED_10_8") (pin "ANODE") (pinfunction "A_ANODE") (pintype "passive"))
      (node (ref "LED_1_8") (pin "ANODE") (pinfunction "A_ANODE") (pintype "passive"))
      (node (ref "LED_2_8") (pin "ANODE") (pinfunction "A_ANODE") (pintype "passive"))
      (node (ref "LED_3_8") (pin "ANODE") (pinfunction "A_ANODE") (pintype "passive"))
      (node (ref "LED_4_8") (pin "ANODE") (pinfunction "A_ANODE") (pintype "passive"))
      (node (ref "LED_5_8") (pin "ANODE") (pinfunction "A_ANODE") (pintype "passive"))
      (node (ref "LED_6_8") (pin "ANODE") (pinfunction "A_ANODE") (pintype "passive"))
      (node (ref "LED_7_8") (pin "ANODE") (pinfunction "A_ANODE") (pintype "passive"))
      (node (ref "LED_8_0") (pin "CATHODE") (pinfunction "C_CATHODE") (pintype "passive"))
      (node (ref "LED_8_1") (pin "CATHODE") (pinfunction "C_CATHODE") (pintype "passive"))
      (node (ref "LED_8_10") (pin "CATHODE") (pinfunction "C_CATHODE") (pintype "passive"))
      (node (ref "LED_8_2") (pin "CATHODE") (pinfunction "C_CATHODE") (pintype "passive"))
      (node (ref "LED_8_3") (pin "CATHODE") (pinfunction "C_CATHODE") (pintype "passive"))
      (node (ref "LED_8_4") (pin "CATHODE") (pinfunction "C_CATHODE") (pintype "passive"))
      (node (ref "LED_8_5") (pin "CATHODE") (pinfunction "C_CATHODE") (pintype "passive"))
      (node (ref "LED_8_6") (pin "CATHODE") (pinfunction "C_CATHODE") (pintype "passive"))
      (node (ref "LED_8_7") (pin "CATHODE") (pinfunction "C_CATHODE") (pintype "passive"))
      (node (ref "LED_8_9") (pin "CATHODE") (pinfunction "C_CATHODE") (pintype "passive"))
      (node (ref "LED_9_8") (pin "ANODE") (pinfunction "A_ANODE") (pintype "passive"))
      (node (ref "U$1") (pin "5") (pinfunction "(PCINT10/INT0/OC0A/CKOUT)PB2_5") (pintype "bidirectional"))
    )
    (net (code "10") (name "/B9") (class "Default")
      (node (ref "LED_0_9") (pin "ANODE") (pinfunction "A_ANODE") (pintype "passive"))
      (node (ref "LED_10_9") (pin "ANODE") (pinfunction "A_ANODE") (pintype "passive"))
      (node (ref "LED_1_9") (pin "ANODE") (pinfunction "A_ANODE") (pintype "passive"))
      (node (ref "LED_2_9") (pin "ANODE") (pinfunction "A_ANODE") (pintype "passive"))
      (node (ref "LED_3_9") (pin "ANODE") (pinfunction "A_ANODE") (pintype "passive"))
      (node (ref "LED_4_9") (pin "ANODE") (pinfunction "A_ANODE") (pintype "passive"))
      (node (ref "LED_5_9") (pin "ANODE") (pinfunction "A_ANODE") (pintype "passive"))
      (node (ref "LED_6_9") (pin "ANODE") (pinfunction "A_ANODE") (pintype "passive"))
      (node (ref "LED_7_9") (pin "ANODE") (pinfunction "A_ANODE") (pintype "passive"))
      (node (ref "LED_8_9") (pin "ANODE") (pinfunction "A_ANODE") (pintype "passive"))
      (node (ref "LED_9_0") (pin "CATHODE") (pinfunction "C_CATHODE") (pintype "passive"))
      (node (ref "LED_9_1") (pin "CATHODE") (pinfunction "C_CATHODE") (pintype "passive"))
      (node (ref "LED_9_10") (pin "CATHODE") (pinfunction "C_CATHODE") (pintype "passive"))
      (node (ref "LED_9_2") (pin "CATHODE") (pinfunction "C_CATHODE") (pintype "passive"))
      (node (ref "LED_9_3") (pin "CATHODE") (pinfunction "C_CATHODE") (pintype "passive"))
      (node (ref "LED_9_4") (pin "CATHODE") (pinfunction "C_CATHODE") (pintype "passive"))
      (node (ref "LED_9_5") (pin "CATHODE") (pinfunction "C_CATHODE") (pintype "passive"))
      (node (ref "LED_9_6") (pin "CATHODE") (pinfunction "C_CATHODE") (pintype "passive"))
      (node (ref "LED_9_7") (pin "CATHODE") (pinfunction "C_CATHODE") (pintype "passive"))
      (node (ref "LED_9_8") (pin "CATHODE") (pinfunction "C_CATHODE") (pintype "passive"))
      (node (ref "U$1") (pin "6") (pinfunction "(PCINT7/ICP/OC0B/ADC7)PA7_6") (pintype "bidirectional"))
    )
    (net (code "11") (name "/B10") (class "Default")
      (node (ref "J1") (pin "4") (pinfunction "MOSI_4") (pintype "passive"))
      (node (ref "LED_0_10") (pin "ANODE") (pinfunction "A_ANODE") (pintype "passive"))
      (node (ref "LED_10_0") (pin "CATHODE") (pinfunction "C_CATHODE") (pintype "passive"))
      (node (ref "LED_10_1") (pin "CATHODE") (pinfunction "C_CATHODE") (pintype "passive"))
      (node (ref "LED_10_2") (pin "CATHODE") (pinfunction "C_CATHODE") (pintype "passive"))
      (node (ref "LED_10_3") (pin "CATHODE") (pinfunction "C_CATHODE") (pintype "passive"))
      (node (ref "LED_10_4") (pin "CATHODE") (pinfunction "C_CATHODE") (pintype "passive"))
      (node (ref "LED_10_5") (pin "CATHODE") (pinfunction "C_CATHODE") (pintype "passive"))
      (node (ref "LED_10_6") (pin "CATHODE") (pinfunction "C_CATHODE") (pintype "passive"))
      (node (ref "LED_10_7") (pin "CATHODE") (pinfunction "C_CATHODE") (pintype "passive"))
      (node (ref "LED_10_8") (pin "CATHODE") (pinfunction "C_CATHODE") (pintype "passive"))
      (node (ref "LED_10_9") (pin "CATHODE") (pinfunction "C_CATHODE") (pintype "passive"))
      (node (ref "LED_1_10") (pin "ANODE") (pinfunction "A_ANODE") (pintype "passive"))
      (node (ref "LED_2_10") (pin "ANODE") (pinfunction "A_ANODE") (pintype "passive"))
      (node (ref "LED_3_10") (pin "ANODE") (pinfunction "A_ANODE") (pintype "passive"))
      (node (ref "LED_4_10") (pin "ANODE") (pinfunction "A_ANODE") (pintype "passive"))
      (node (ref "LED_5_10") (pin "ANODE") (pinfunction "A_ANODE") (pintype "passive"))
      (node (ref "LED_6_10") (pin "ANODE") (pinfunction "A_ANODE") (pintype "passive"))
      (node (ref "LED_7_10") (pin "ANODE") (pinfunction "A_ANODE") (pintype "passive"))
      (node (ref "LED_8_10") (pin "ANODE") (pinfunction "A_ANODE") (pintype "passive"))
      (node (ref "LED_9_10") (pin "ANODE") (pinfunction "A_ANODE") (pintype "passive"))
      (node (ref "U$1") (pin "7") (pinfunction "(PCINT6/OC1A/SDA/MOSI/ADC6)PA6_7") (pintype "bidirectional"))
    )
    (net (code "12") (name "/RST") (class "Default")
      (node (ref "J1") (pin "5") (pinfunction "RST_5") (pintype "passive"))
      (node (ref "S1") (pin "3") (pinfunction "3_3") (pintype "passive"))
      (node (ref "S1") (pin "4") (pinfunction "4_4") (pintype "passive"))
      (node (ref "U$1") (pin "4") (pinfunction "(PCINT11/~{RESET/DW})PB3_4") (pintype "bidirectional"))
    )
    (net (code "13") (name "5V") (class "Default")
      (node (ref "BAT1") (pin "PWR@1") (pinfunction "+_PWR@1") (pintype "power_in"))
      (node (ref "C1") (pin "1") (pinfunction "1_1") (pintype "passive"))
      (node (ref "C2") (pin "1") (pinfunction "+_1") (pintype "passive"))
      (node (ref "J1") (pin "2") (pinfunction "V+_2") (pintype "passive"))
      (node (ref "U$1") (pin "1") (pinfunction "VCC_1") (pintype "bidirectional"))
      (node (ref "U$2") (pin "+") (pinfunction "+_+") (pintype "power_in"))
      (node (ref "U$3") (pin "+2") (pinfunction "+1_+2") (pintype "passive"))
    )
    (net (code "14") (name "GND") (class "Default")
      (node (ref "BAT2") (pin "GND@1") (pinfunction "-_GND@1") (pintype "power_in"))
      (node (ref "C1") (pin "2") (pinfunction "2_2") (pintype "passive"))
      (node (ref "C2") (pin "2") (pinfunction "-_2") (pintype "passive"))
      (node (ref "J1") (pin "6") (pinfunction "GND_6") (pintype "passive"))
      (node (ref "S1") (pin "1") (pinfunction "1_1") (pintype "passive"))
      (node (ref "S1") (pin "2") (pinfunction "2_2") (pintype "passive"))
      (node (ref "U$1") (pin "14") (pinfunction "GND_14") (pintype "bidirectional"))
      (node (ref "U$2") (pin "-") (pinfunction "-_-") (pintype "power_in"))
      (node (ref "U$3") (pin "-") (pinfunction "-_-") (pintype "passive"))
    )
    (net (code "15") (name "Net-(BAT1--)") (class "Default")
      (node (ref "BAT1") (pin "GND@1") (pinfunction "-_GND@1") (pintype "power_in"))
      (node (ref "BAT2") (pin "PWR@1") (pinfunction "+_PWR@1") (pintype "power_in"))
    )
    (net (code "16") (name "unconnected-(U$3-+-Pad+1)") (class "Default")
      (node (ref "U$3") (pin "+1") (pinfunction "+_+1") (pintype "passive"))
    )
  )
)
